# Sheet1.net
KiCad netlist of a schematic drawn in Altium Designer
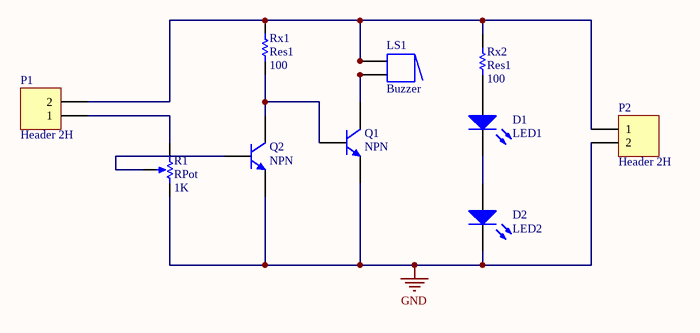
[diagram p0: Sheet1.SchDoc]

(export (version "E")
  (design (tool "Eeschema 10.0.6"))
  (components
    (comp (ref "D1")
      (value "LED1")
      (footprint "LED-1")
      (description "Typical RED GaAs LED")
      (fields (field (name "PUBLISHER") "Altium Limited"))
      (libsource (lib "Miscellaneous Devices") (part "LED1"))
    )
    (comp (ref "D2")
      (value "LED2")
      (footprint "LED-1")
      (description "Typical RED GaAs LED")
      (fields (field (name "PUBLISHER") "Altium Limited"))
      (libsource (lib "Miscellaneous Devices") (part "LED1"))
    )
    (comp (ref "LS1")
      (value "Buzzer")
      (footprint "ABSM-1574")
      (description "Magnetic Transducer Buzzer")
      (fields (field (name "PUBLISHER") "Altium Limited"))
      (libsource (lib "Miscellaneous Devices") (part "Buzzer"))
    )
    (comp (ref "P1")
      (value "Header 2H")
      (footprint "HDR1X2H")
      (description "Header, 2-Pin, Right Angle")
      (fields (field (name "PUBLISHER") "Altium Limited"))
      (libsource (lib "Miscellaneous Connectors") (part "Header 2H"))
    )
    (comp (ref "P2")
      (value "Header 2H")
      (footprint "HDR1X2H")
      (description "Header, 2-Pin, Right Angle")
      (fields (field (name "PUBLISHER") "Altium Limited"))
      (libsource (lib "") (part "Header 2H_1"))
    )
    (comp (ref "Q1")
      (value "NPN")
      (footprint "TO-226-AA")
      (description "NPN Bipolar Transistor")
      (fields (field (name "PUBLISHER") "Altium Limited"))
      (libsource (lib "Miscellaneous Devices") (part "NPN"))
    )
    (comp (ref "Q2")
      (value "NPN")
      (footprint "TO-226-AA")
      (description "NPN Bipolar Transistor")
      (fields (field (name "PUBLISHER") "Altium Limited"))
      (libsource (lib "Miscellaneous Devices") (part "NPN"))
    )
    (comp (ref "R1")
      (value "RPot")
      (footprint "VR5")
      (description "Potentiometer")
      (fields (field (name "ALTIUM_VALUE") "1K") (field (name "PUBLISHER") "Altium Limited"))
      (libsource (lib "Miscellaneous Devices") (part "RPot"))
    )
    (comp (ref "Rx1")
      (value "Res1")
      (footprint "AXIAL-0.1-RES")
      (description "Resistor")
      (fields
        (field (name "ALTIUM_VALUE") "100")
        (field (name "MANUFACTURER PART NUMBER") "CFR-25JB-52-100R")
        (field (name "TOLERANCE") "0.05")
        (field (name "PUBLISHER") "Altium Limited")
      )
      (libsource (lib "ECE295-Resistors-TH") (part "RES 100 OHM 5% 1/4W AXIAL"))
    )
    (comp (ref "Rx2")
      (value "Res1")
      (footprint "AXIAL-0.1-RES")
      (description "Resistor")
      (fields
        (field (name "ALTIUM_VALUE") "100")
        (field (name "MANUFACTURER PART NUMBER") "CFR-25JB-52-100R")
        (field (name "TOLERANCE") "0.05")
        (field (name "PUBLISHER") "Altium Limited")
      )
      (libsource (lib "ECE295-Resistors-TH") (part "RES 100 OHM 5% 1/4W AXIAL"))
    )
  )
  (nets
    (net (code "1") (name "GND") (class "Default")
      (node (ref "D2") (pin "2") (pinfunction "K_2") (pintype "passive"))
      (node (ref "P2") (pin "2") (pinfunction "2_2") (pintype "passive"))
      (node (ref "Q1") (pin "3") (pinfunction "E_3") (pintype "passive"))
      (node (ref "Q2") (pin "3") (pinfunction "E_3") (pintype "passive"))
      (node (ref "R1") (pin "2") (pinfunction "BOT_2") (pintype "passive"))
    )
    (net (code "2") (name "Net-(D1-A)") (class "Default")
      (node (ref "D1") (pin "1") (pinfunction "A_1") (pintype "passive"))
      (node (ref "Rx2") (pin "1") (pinfunction "1_1") (pintype "passive"))
    )
    (net (code "3") (name "Net-(D1-K)") (class "Default")
      (node (ref "D1") (pin "2") (pinfunction "K_2") (pintype "passive"))
      (node (ref "D2") (pin "1") (pinfunction "A_1") (pintype "passive"))
    )
    (net (code "4") (name "Net-(LS1-Pad1)") (class "Default")
      (node (ref "LS1") (pin "1") (pinfunction "1_1") (pintype "passive"))
      (node (ref "LS1") (pin "1A") (pinfunction "1A_1A") (pintype "passive"))
      (node (ref "P1") (pin "2") (pinfunction "2_2") (pintype "passive"))
      (node (ref "P2") (pin "1") (pinfunction "1_1") (pintype "passive"))
      (node (ref "Rx1") (pin "2") (pinfunction "2_2") (pintype "passive"))
      (node (ref "Rx2") (pin "2") (pinfunction "2_2") (pintype "passive"))
    )
    (net (code "5") (name "Net-(Q1-B)") (class "Default")
      (node (ref "Q1") (pin "2") (pinfunction "B_2") (pintype "passive"))
      (node (ref "Q2") (pin "1") (pinfunction "C_1") (pintype "passive"))
      (node (ref "Rx1") (pin "1") (pinfunction "1_1") (pintype "passive"))
    )
    (net (code "6") (name "Net-(Q1-C)") (class "Default")
      (node (ref "LS1") (pin "2") (pinfunction "2_2") (pintype "passive"))
      (node (ref "LS1") (pin "2A") (pinfunction "2A_2A") (pintype "passive"))
      (node (ref "Q1") (pin "1") (pinfunction "C_1") (pintype "passive"))
    )
    (net (code "7") (name "Net-(Q2-B)") (class "Default")
      (node (ref "Q2") (pin "2") (pinfunction "B_2") (pintype "passive"))
      (node (ref "R1") (pin "3") (pinfunction "TAP_3") (pintype "passive"))
    )
    (net (code "8") (name "Net-(R1-TOP)") (class "Default")
      (node (ref "P1") (pin "1") (pinfunction "1_1") (pintype "passive"))
      (node (ref "R1") (pin "1") (pinfunction "TOP_1") (pintype "passive"))
    )
  )
)
